# Power_supply_schematic.net
KiCad netlist of a schematic drawn in EAGLE
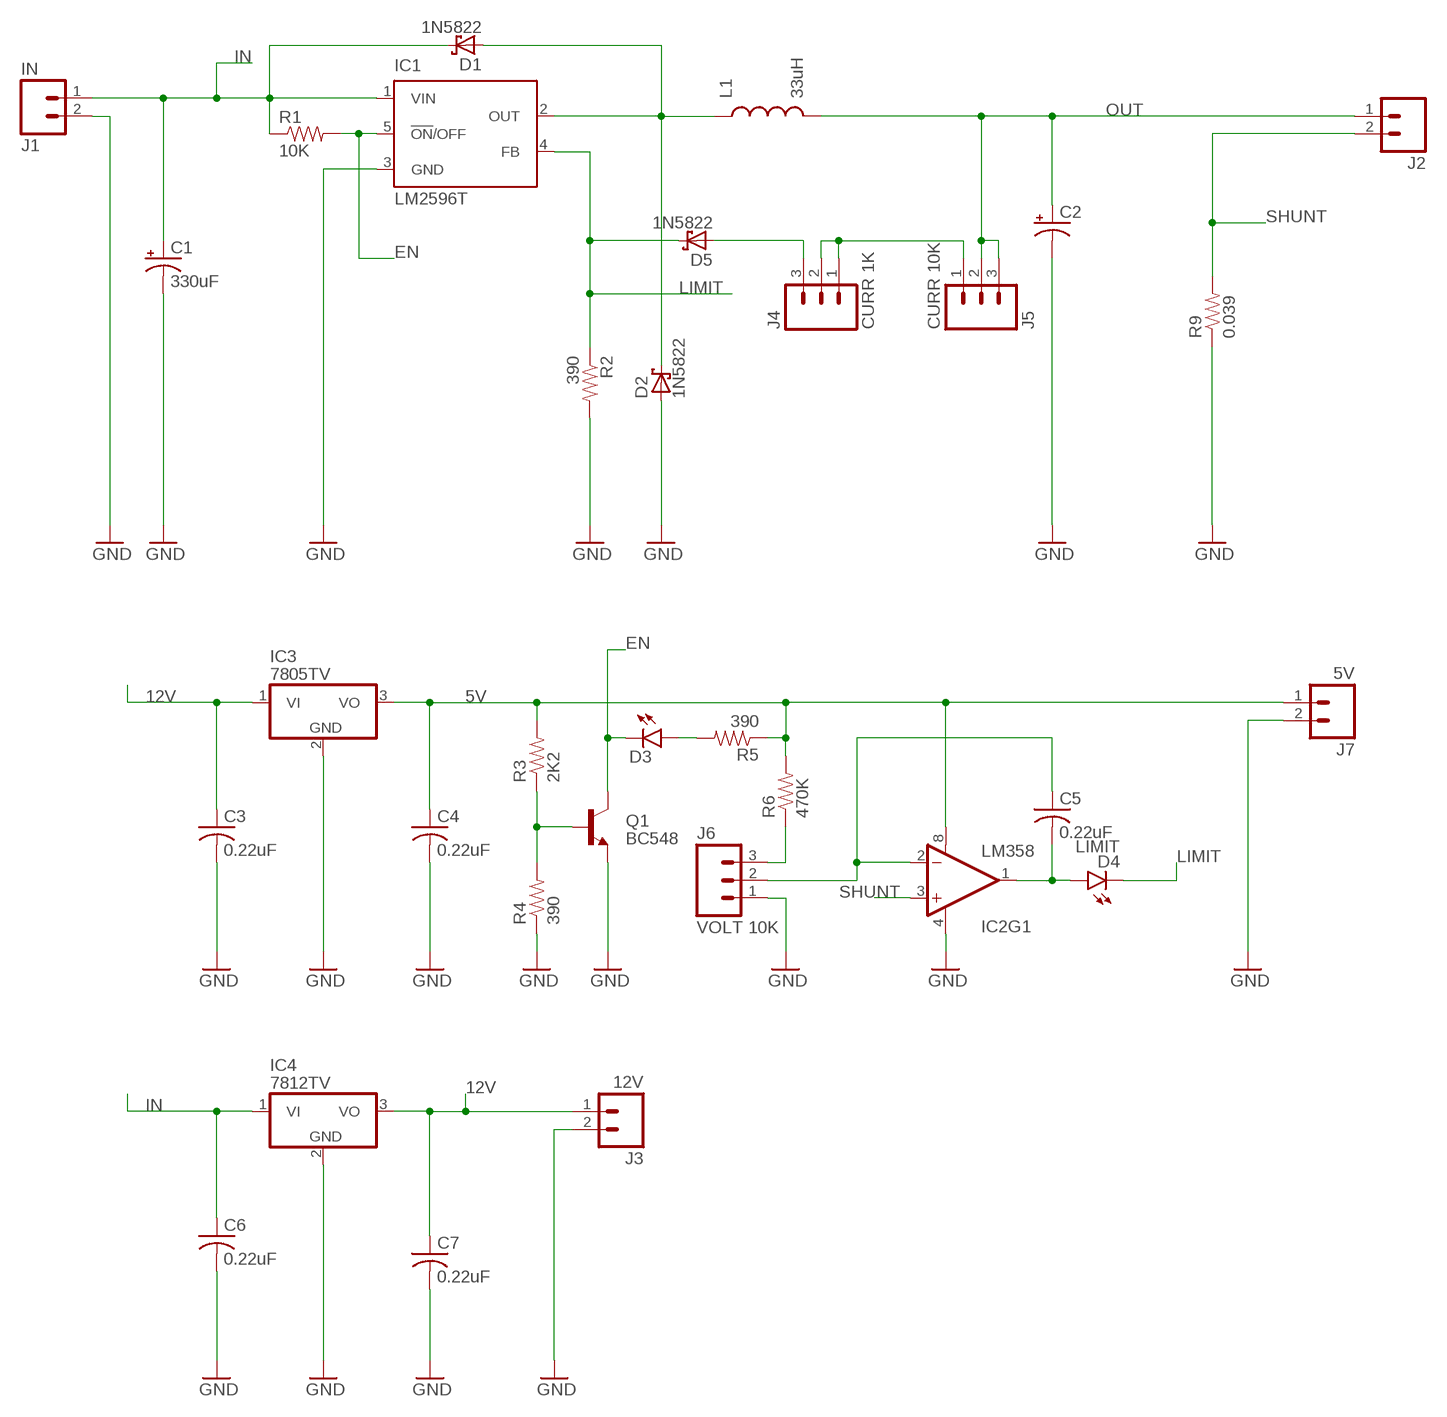
[diagram p0: schematic, sheet 1]

(export (version "E")
  (design (tool "Eeschema 10.0.6"))
  (components
    (comp (ref "C1")
      (value "330uF")
      (footprint "eagle-import:CPOL-RADIAL-1000UF-25V")
      (libsource (lib "eagle-import") (part "CAP_POLPTH4"))
    )
    (comp (ref "C2")
      (value "CAP_POLPTH4")
      (footprint "eagle-import:CPOL-RADIAL-1000UF-25V")
      (libsource (lib "eagle-import") (part "CAP_POLPTH4"))
    )
    (comp (ref "C3")
      (value "0.22uF")
      (footprint "eagle-import:C050-025X075")
      (libsource (lib "eagle-import") (part "C-US050-025X075"))
    )
    (comp (ref "C4")
      (value "0.22uF")
      (footprint "eagle-import:C050-025X075")
      (libsource (lib "eagle-import") (part "C-US050-025X075"))
    )
    (comp (ref "C5")
      (value "0.22uF")
      (footprint "eagle-import:C050-025X075")
      (libsource (lib "eagle-import") (part "C-US050-025X075"))
    )
    (comp (ref "C6")
      (value "0.22uF")
      (footprint "eagle-import:C050-025X075")
      (libsource (lib "eagle-import") (part "C-US050-025X075"))
    )
    (comp (ref "C7")
      (value "0.22uF")
      (footprint "eagle-import:C050-025X075")
      (libsource (lib "eagle-import") (part "C-US050-025X075"))
    )
    (comp (ref "D1")
      (value "1N5822")
      (footprint "eagle-import:DO201T15")
      (libsource (lib "eagle-import") (part "SCHOTTKY-DIODEDO201T15"))
    )
    (comp (ref "D2")
      (value "1N5822")
      (footprint "eagle-import:DO201T15")
      (libsource (lib "eagle-import") (part "SCHOTTKY-DIODEDO201T15"))
    )
    (comp (ref "D3")
      (value "LED3MM")
      (footprint "eagle-import:LED3MM")
      (libsource (lib "eagle-import") (part "LED3MM"))
    )
    (comp (ref "D4")
      (value "LIMIT")
      (footprint "eagle-import:LED3MM")
      (libsource (lib "eagle-import") (part "LED3MM"))
    )
    (comp (ref "D5")
      (value "1N5822")
      (footprint "eagle-import:DO201T15")
      (libsource (lib "eagle-import") (part "SCHOTTKY-DIODEDO201T15"))
    )
    (comp (ref "IC1")
      (value "LM2596T")
      (footprint "eagle-import:T05D")
      (fields (field (name "MPN") "LM2596T-ADJ/LF02"))
      (libsource (lib "eagle-import") (part "LM2596T"))
    )
    (comp (ref "IC2")
      (value "LM358")
      (footprint "eagle-import:DIP08")
      (libsource (lib "eagle-import") (part "LM358"))
    )
    (comp (ref "IC3")
      (value "7805TV")
      (footprint "eagle-import:TO220V")
      (libsource (lib "eagle-import") (part "78TV05"))
    )
    (comp (ref "IC4")
      (value "7812TV")
      (footprint "eagle-import:TO220V")
      (libsource (lib "eagle-import") (part "78TV12"))
    )
    (comp (ref "J1")
      (value "IN")
      (footprint "eagle-import:SCREWTERMINAL-5MM-2")
      (libsource (lib "eagle-import") (part "M025MM"))
    )
    (comp (ref "J2")
      (value "M025MM")
      (footprint "eagle-import:SCREWTERMINAL-5MM-2")
      (libsource (lib "eagle-import") (part "M025MM"))
    )
    (comp (ref "J3")
      (value "12V")
      (footprint "eagle-import:SCREWTERMINAL-5MM-2")
      (libsource (lib "eagle-import") (part "M025MM"))
    )
    (comp (ref "J4")
      (value "CURR 1K")
      (footprint "eagle-import:MOLEX-1X3")
      (libsource (lib "eagle-import") (part "M03POLAR"))
    )
    (comp (ref "J5")
      (value "CURR 10K")
      (footprint "eagle-import:MOLEX-1X3")
      (libsource (lib "eagle-import") (part "M03POLAR"))
    )
    (comp (ref "J6")
      (value "VOLT 10K")
      (footprint "eagle-import:MOLEX-1X3")
      (libsource (lib "eagle-import") (part "M03POLAR"))
    )
    (comp (ref "J7")
      (value "5V")
      (footprint "eagle-import:SCREWTERMINAL-5MM-2")
      (fields (field (name "STOREFRONT_ID") "PRT-08432"))
      (libsource (lib "eagle-import") (part "M025MM"))
    )
    (comp (ref "L1")
      (value "33uH")
      (footprint "eagle-import:RLB0912")
      (libsource (lib "eagle-import") (part "INDUCTORRLB0912"))
    )
    (comp (ref "Q1")
      (value "BC548")
      (footprint "eagle-import:TO-92-AMMO")
      (libsource (lib "eagle-import") (part "TRANSISTOR_NPNBC547"))
    )
    (comp (ref "R1")
      (value "10K")
      (footprint "eagle-import:AXIAL-0.4")
      (libsource (lib "eagle-import") (part "RESISTORPTH-1/4W"))
    )
    (comp (ref "R2")
      (value "390")
      (footprint "eagle-import:AXIAL-0.4")
      (libsource (lib "eagle-import") (part "RESISTORPTH-1/4W"))
    )
    (comp (ref "R3")
      (value "2K2")
      (footprint "eagle-import:AXIAL-0.4")
      (libsource (lib "eagle-import") (part "RESISTORPTH-1/4W"))
    )
    (comp (ref "R4")
      (value "390")
      (footprint "eagle-import:AXIAL-0.4")
      (libsource (lib "eagle-import") (part "RESISTORPTH-1/4W"))
    )
    (comp (ref "R5")
      (value "390")
      (footprint "eagle-import:AXIAL-0.4")
      (libsource (lib "eagle-import") (part "RESISTORPTH-1/4W"))
    )
    (comp (ref "R6")
      (value "470K")
      (footprint "eagle-import:AXIAL-0.4")
      (libsource (lib "eagle-import") (part "RESISTORPTH-1/4W"))
    )
    (comp (ref "R9")
      (value "0.039")
      (footprint "eagle-import:AXIAL-0.6")
      (libsource (lib "eagle-import") (part "RESISTORPTH-1W"))
    )
  )
  (nets
    (net (code "1") (name "/5V") (class "Default")
      (node (ref "C4") (pin "1") (pinfunction "1_1") (pintype "passive"))
      (node (ref "IC2") (pin "8") (pinfunction "V+_8") (pintype "power_in"))
      (node (ref "IC3") (pin "3") (pinfunction "VO_3") (pintype "passive"))
      (node (ref "J7") (pin "1") (pinfunction "1_1") (pintype "passive"))
      (node (ref "R3") (pin "P$2") (pinfunction "2_P$2") (pintype "passive"))
      (node (ref "R5") (pin "P$1") (pinfunction "1_P$1") (pintype "passive"))
      (node (ref "R6") (pin "P$2") (pinfunction "2_P$2") (pintype "passive"))
    )
    (net (code "2") (name "/12V") (class "Default")
      (node (ref "C3") (pin "1") (pinfunction "1_1") (pintype "passive"))
      (node (ref "C7") (pin "1") (pinfunction "1_1") (pintype "passive"))
      (node (ref "IC3") (pin "1") (pinfunction "VI_1") (pintype "input"))
      (node (ref "IC4") (pin "3") (pinfunction "VO_3") (pintype "passive"))
      (node (ref "J3") (pin "1") (pinfunction "1_1") (pintype "passive"))
    )
    (net (code "3") (name "/EN") (class "Default")
      (node (ref "D3") (pin "K") (pinfunction "C_K") (pintype "passive"))
      (node (ref "IC1") (pin "5") (pinfunction "~{ON}/OFF_5") (pintype "input"))
      (node (ref "Q1") (pin "1") (pinfunction "C_1") (pintype "passive"))
      (node (ref "R1") (pin "P$2") (pinfunction "2_P$2") (pintype "passive"))
    )
    (net (code "4") (name "/IN") (class "Default")
      (node (ref "C1") (pin "+") (pinfunction "+_+") (pintype "passive"))
      (node (ref "C6") (pin "1") (pinfunction "1_1") (pintype "passive"))
      (node (ref "D1") (pin "C") (pinfunction "C_C") (pintype "passive"))
      (node (ref "IC1") (pin "1") (pinfunction "VIN_1") (pintype "input"))
      (node (ref "IC4") (pin "1") (pinfunction "VI_1") (pintype "input"))
      (node (ref "J1") (pin "1") (pinfunction "1_1") (pintype "passive"))
      (node (ref "R1") (pin "P$1") (pinfunction "1_P$1") (pintype "passive"))
    )
    (net (code "5") (name "/LIMIT") (class "Default")
      (node (ref "D4") (pin "K") (pinfunction "C_K") (pintype "passive"))
      (node (ref "D5") (pin "C") (pinfunction "C_C") (pintype "passive"))
      (node (ref "IC1") (pin "4") (pinfunction "FB_4") (pintype "input"))
      (node (ref "R2") (pin "P$1") (pinfunction "1_P$1") (pintype "passive"))
    )
    (net (code "6") (name "/OUT") (class "Default")
      (node (ref "C2") (pin "+") (pinfunction "+_+") (pintype "passive"))
      (node (ref "J2") (pin "1") (pinfunction "1_1") (pintype "passive"))
      (node (ref "J5") (pin "2") (pinfunction "2_2") (pintype "passive"))
      (node (ref "J5") (pin "3") (pinfunction "3_3") (pintype "passive"))
      (node (ref "L1") (pin "2") (pinfunction "2_2") (pintype "passive"))
    )
    (net (code "7") (name "/SHUNT") (class "Default")
      (node (ref "IC2") (pin "3") (pinfunction "+IN_3") (pintype "input"))
      (node (ref "J2") (pin "2") (pinfunction "2_2") (pintype "passive"))
      (node (ref "R9") (pin "P$2") (pinfunction "2_P$2") (pintype "passive"))
    )
    (net (code "8") (name "GND") (class "Default")
      (node (ref "C1") (pin "-") (pinfunction "-_-") (pintype "passive"))
      (node (ref "C2") (pin "-") (pinfunction "-_-") (pintype "passive"))
      (node (ref "C3") (pin "2") (pinfunction "2_2") (pintype "passive"))
      (node (ref "C4") (pin "2") (pinfunction "2_2") (pintype "passive"))
      (node (ref "C6") (pin "2") (pinfunction "2_2") (pintype "passive"))
      (node (ref "C7") (pin "2") (pinfunction "2_2") (pintype "passive"))
      (node (ref "D2") (pin "A") (pinfunction "A_A") (pintype "passive"))
      (node (ref "IC1") (pin "3") (pinfunction "GND_3") (pintype "power_in"))
      (node (ref "IC2") (pin "4") (pinfunction "V-_4") (pintype "power_in"))
      (node (ref "IC3") (pin "2") (pinfunction "GND_2") (pintype "passive"))
      (node (ref "IC4") (pin "2") (pinfunction "GND_2") (pintype "passive"))
      (node (ref "J1") (pin "2") (pinfunction "2_2") (pintype "passive"))
      (node (ref "J3") (pin "2") (pinfunction "2_2") (pintype "passive"))
      (node (ref "J6") (pin "1") (pinfunction "1_1") (pintype "passive"))
      (node (ref "J7") (pin "2") (pinfunction "2_2") (pintype "passive"))
      (node (ref "Q1") (pin "3") (pinfunction "E_3") (pintype "passive"))
      (node (ref "R2") (pin "P$2") (pinfunction "2_P$2") (pintype "passive"))
      (node (ref "R4") (pin "P$1") (pinfunction "1_P$1") (pintype "passive"))
      (node (ref "R9") (pin "P$1") (pinfunction "1_P$1") (pintype "passive"))
    )
    (net (code "9") (name "Net-(D5-PadA)") (class "Default")
      (node (ref "D5") (pin "A") (pinfunction "A_A") (pintype "passive"))
      (node (ref "J4") (pin "3") (pinfunction "3_3") (pintype "passive"))
    )
    (net (code "10") (name "Net-(IC1-OUT)") (class "Default")
      (node (ref "D1") (pin "A") (pinfunction "A_A") (pintype "passive"))
      (node (ref "D2") (pin "C") (pinfunction "C_C") (pintype "passive"))
      (node (ref "IC1") (pin "2") (pinfunction "OUT_2") (pintype "output"))
      (node (ref "L1") (pin "1") (pinfunction "1_1") (pintype "passive"))
    )
    (net (code "11") (name "Net-(IC2A--IN)") (class "Default")
      (node (ref "C5") (pin "1") (pinfunction "1_1") (pintype "passive"))
      (node (ref "IC2") (pin "2") (pinfunction "-IN_2") (pintype "input"))
      (node (ref "J6") (pin "2") (pinfunction "2_2") (pintype "passive"))
    )
    (net (code "12") (name "Net-(IC2A-OUT)") (class "Default")
      (node (ref "C5") (pin "2") (pinfunction "2_2") (pintype "passive"))
      (node (ref "D4") (pin "A") (pinfunction "A_A") (pintype "passive"))
      (node (ref "IC2") (pin "1") (pinfunction "OUT_1") (pintype "output"))
    )
    (net (code "13") (name "Net-(J4-Pad1)") (class "Default")
      (node (ref "J4") (pin "1") (pinfunction "1_1") (pintype "passive"))
      (node (ref "J4") (pin "2") (pinfunction "2_2") (pintype "passive"))
      (node (ref "J5") (pin "1") (pinfunction "1_1") (pintype "passive"))
    )
    (net (code "14") (name "Net-(Q1-B)") (class "Default")
      (node (ref "Q1") (pin "2") (pinfunction "B_2") (pintype "passive"))
      (node (ref "R3") (pin "P$1") (pinfunction "1_P$1") (pintype "passive"))
      (node (ref "R4") (pin "P$2") (pinfunction "2_P$2") (pintype "passive"))
    )
    (net (code "15") (name "Net-(R5-2)") (class "Default")
      (node (ref "D3") (pin "A") (pinfunction "A_A") (pintype "passive"))
      (node (ref "R5") (pin "P$2") (pinfunction "2_P$2") (pintype "passive"))
    )
    (net (code "16") (name "Net-(R6-1)") (class "Default")
      (node (ref "J6") (pin "3") (pinfunction "3_3") (pintype "passive"))
      (node (ref "R6") (pin "P$1") (pinfunction "1_P$1") (pintype "passive"))
    )
  )
)
